# BlancerCarMotoDriver.net
KiCad netlist of a schematic drawn in Altium Designer
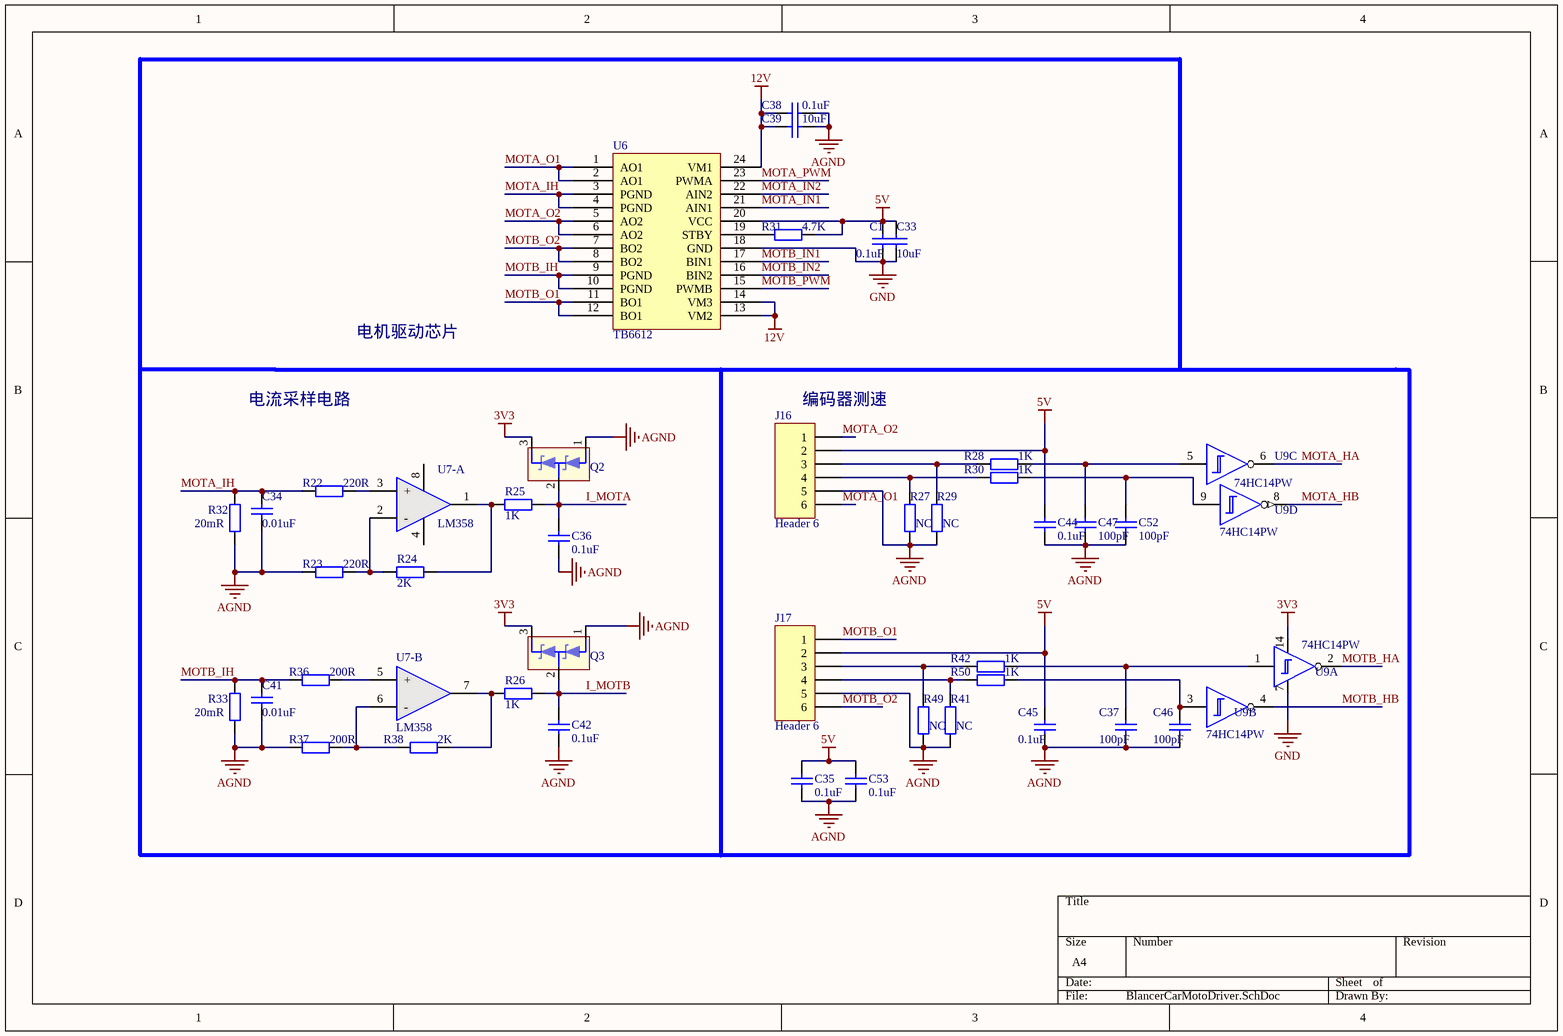
[diagram p0: BlancerCarMotoDriver.SchDoc]

(export (version "E")
  (design (tool "Eeschema 10.0.6"))
  (components
    (comp (ref "C1")
      (value "0.1uF")
      (footprint "0805-1")
      (description "Capacitor")
      (fields (field (name "Comment") "Cap") (field (name "PUBLISHER") "Altium Limited"))
      (libsource (lib "BlancerCar") (part "Cap"))
    )
    (comp (ref "C33")
      (value "10uF")
      (footprint "0805-1")
      (description "Capacitor")
      (fields (field (name "Comment") "Cap") (field (name "PUBLISHER") "Altium Limited"))
      (libsource (lib "BlancerCar") (part "Cap"))
    )
    (comp (ref "C34")
      (value "0.01uF")
      (footprint "0805-1")
      (description "Capacitor")
      (fields (field (name "Comment") "Cap") (field (name "PUBLISHER") "Altium Limited"))
      (libsource (lib "BlancerCar") (part "Cap"))
    )
    (comp (ref "C35")
      (value "0.1uF")
      (footprint "0805-1")
      (description "Capacitor")
      (fields (field (name "Comment") "Cap") (field (name "PUBLISHER") "Altium Limited"))
      (libsource (lib "BlancerCar") (part "Cap"))
    )
    (comp (ref "C36")
      (value "0.1uF")
      (footprint "0805-1")
      (description "Capacitor")
      (fields (field (name "Comment") "Cap") (field (name "PUBLISHER") "Altium Limited"))
      (libsource (lib "BlancerCar") (part "Cap"))
    )
    (comp (ref "C37")
      (value "100pF")
      (footprint "0805-1")
      (description "Capacitor")
      (fields (field (name "Comment") "Cap") (field (name "PUBLISHER") "Altium Limited"))
      (libsource (lib "BlancerCar") (part "Cap"))
    )
    (comp (ref "C38")
      (value "0.1uF")
      (footprint "0805-1")
      (description "Capacitor")
      (fields (field (name "Comment") "Cap") (field (name "PUBLISHER") "Altium Limited"))
      (libsource (lib "BlancerCar") (part "Cap"))
    )
    (comp (ref "C39")
      (value "10uF")
      (footprint "0805-1")
      (description "Capacitor")
      (fields (field (name "Comment") "Cap") (field (name "PUBLISHER") "Altium Limited"))
      (libsource (lib "BlancerCar") (part "Cap"))
    )
    (comp (ref "C41")
      (value "0.01uF")
      (footprint "0805-1")
      (description "Capacitor")
      (fields (field (name "Comment") "Cap") (field (name "PUBLISHER") "Altium Limited"))
      (libsource (lib "BlancerCar") (part "Cap"))
    )
    (comp (ref "C42")
      (value "0.1uF")
      (footprint "0805-1")
      (description "Capacitor")
      (fields (field (name "Comment") "Cap") (field (name "PUBLISHER") "Altium Limited"))
      (libsource (lib "BlancerCar") (part "Cap"))
    )
    (comp (ref "C44")
      (value "0.1uF")
      (footprint "0805-1")
      (description "Capacitor")
      (fields (field (name "Comment") "Cap") (field (name "PUBLISHER") "Altium Limited"))
      (libsource (lib "BlancerCar") (part "Cap"))
    )
    (comp (ref "C45")
      (value "0.1uF")
      (footprint "0805-1")
      (description "Capacitor")
      (fields (field (name "Comment") "Cap") (field (name "PUBLISHER") "Altium Limited"))
      (libsource (lib "BlancerCar") (part "Cap"))
    )
    (comp (ref "C46")
      (value "100pF")
      (footprint "0805-1")
      (description "Capacitor")
      (fields (field (name "Comment") "Cap") (field (name "PUBLISHER") "Altium Limited"))
      (libsource (lib "BlancerCar") (part "Cap"))
    )
    (comp (ref "C47")
      (value "100pF")
      (footprint "0805-1")
      (description "Capacitor")
      (fields (field (name "Comment") "Cap") (field (name "PUBLISHER") "Altium Limited"))
      (libsource (lib "BlancerCar") (part "Cap"))
    )
    (comp (ref "C52")
      (value "100pF")
      (footprint "0805-1")
      (description "Capacitor")
      (fields (field (name "Comment") "Cap") (field (name "PUBLISHER") "Altium Limited"))
      (libsource (lib "BlancerCar") (part "Cap"))
    )
    (comp (ref "C53")
      (value "0.1uF")
      (footprint "0805-1")
      (description "Capacitor")
      (fields (field (name "Comment") "Cap") (field (name "PUBLISHER") "Altium Limited"))
      (libsource (lib "BlancerCar") (part "Cap"))
    )
    (comp (ref "J16")
      (value "Header 6")
      (footprint "HDR1X6")
      (description "Header, 6-Pin")
      (fields (field (name "PUBLISHER") "Altium Limited"))
      (libsource (lib "Miscellaneous Connectors") (part "Header 6"))
    )
    (comp (ref "J17")
      (value "Header 6")
      (footprint "HDR1X6")
      (description "Header, 6-Pin")
      (fields (field (name "PUBLISHER") "Altium Limited"))
      (libsource (lib "Miscellaneous Connectors") (part "Header 6"))
    )
    (comp (ref "Q2")
      (value "肖基特二极管")
      (footprint "BAT54S(SOT-23-3)")
      (libsource (lib "BlancerCar") (part "BAT54S"))
    )
    (comp (ref "Q3")
      (value "肖基特二极管")
      (footprint "BAT54S(SOT-23-3)")
      (libsource (lib "BlancerCar") (part "BAT54S"))
    )
    (comp (ref "R22")
      (value "220R")
      (footprint "0805-1")
      (description "贴片电阻")
      (fields (field (name "Comment") "Res1") (field (name "PUBLISHER") "Altium Limited"))
      (libsource (lib "xdhADL") (part "Res1"))
    )
    (comp (ref "R23")
      (value "220R")
      (footprint "0805-1")
      (description "贴片电阻")
      (fields (field (name "Comment") "Res1") (field (name "PUBLISHER") "Altium Limited"))
      (libsource (lib "xdhADL") (part "Res1"))
    )
    (comp (ref "R24")
      (value "2K")
      (footprint "0805-1")
      (description "贴片电阻")
      (fields (field (name "Comment") "Res1") (field (name "PUBLISHER") "Altium Limited"))
      (libsource (lib "xdhADL") (part "Res1"))
    )
    (comp (ref "R25")
      (value "1K")
      (footprint "0805-1")
      (description "贴片电阻")
      (fields (field (name "Comment") "Res1") (field (name "PUBLISHER") "Altium Limited"))
      (libsource (lib "xdhADL") (part "Res1"))
    )
    (comp (ref "R26")
      (value "1K")
      (footprint "0805-1")
      (description "贴片电阻")
      (fields (field (name "Comment") "Res1") (field (name "PUBLISHER") "Altium Limited"))
      (libsource (lib "") (part "Res1_1"))
    )
    (comp (ref "R27")
      (value "NC")
      (footprint "0805-1")
      (description "贴片电阻")
      (fields (field (name "Comment") "Res1") (field (name "PUBLISHER") "Altium Limited"))
      (libsource (lib "") (part "Res1_2"))
    )
    (comp (ref "R28")
      (value "1K")
      (footprint "0805-1")
      (description "贴片电阻")
      (fields (field (name "Comment") "Res1") (field (name "PUBLISHER") "Altium Limited"))
      (libsource (lib "xdhADL") (part "Res1"))
    )
    (comp (ref "R29")
      (value "NC")
      (footprint "0805-1")
      (description "贴片电阻")
      (fields (field (name "Comment") "Res1") (field (name "PUBLISHER") "Altium Limited"))
      (libsource (lib "") (part "Res1_2"))
    )
    (comp (ref "R30")
      (value "1K")
      (footprint "0805-1")
      (description "贴片电阻")
      (fields (field (name "Comment") "Res1") (field (name "PUBLISHER") "Altium Limited"))
      (libsource (lib "xdhADL") (part "Res1"))
    )
    (comp (ref "R31")
      (value "4.7K")
      (footprint "0805-1")
      (description "贴片电阻")
      (fields (field (name "Comment") "Res1") (field (name "PUBLISHER") "Altium Limited"))
      (libsource (lib "xdhADL") (part "Res1"))
    )
    (comp (ref "R32")
      (value "20mR")
      (footprint "0805-1")
      (description "贴片电阻")
      (fields (field (name "Comment") "Res1") (field (name "PUBLISHER") "Altium Limited"))
      (libsource (lib "xdhADL") (part "Res1"))
    )
    (comp (ref "R33")
      (value "20mR")
      (footprint "0805-1")
      (description "贴片电阻")
      (fields (field (name "Comment") "Res1") (field (name "PUBLISHER") "Altium Limited"))
      (libsource (lib "") (part "Res1_2"))
    )
    (comp (ref "R36")
      (value "200R")
      (footprint "0805-1")
      (description "贴片电阻")
      (fields (field (name "Comment") "Res1") (field (name "PUBLISHER") "Altium Limited"))
      (libsource (lib "") (part "Res1_1"))
    )
    (comp (ref "R37")
      (value "200R")
      (footprint "0805-1")
      (description "贴片电阻")
      (fields (field (name "Comment") "Res1") (field (name "PUBLISHER") "Altium Limited"))
      (libsource (lib "") (part "Res1_1"))
    )
    (comp (ref "R38")
      (value "2K")
      (footprint "0805-1")
      (description "贴片电阻")
      (fields (field (name "Comment") "Res1") (field (name "PUBLISHER") "Altium Limited"))
      (libsource (lib "") (part "Res1_1"))
    )
    (comp (ref "R41")
      (value "NC")
      (footprint "0805-1")
      (description "贴片电阻")
      (fields (field (name "Comment") "Res1") (field (name "PUBLISHER") "Altium Limited"))
      (libsource (lib "") (part "Res1_2"))
    )
    (comp (ref "R42")
      (value "1K")
      (footprint "0805-1")
      (description "贴片电阻")
      (fields (field (name "Comment") "Res1") (field (name "PUBLISHER") "Altium Limited"))
      (libsource (lib "xdhADL") (part "Res1"))
    )
    (comp (ref "R49")
      (value "NC")
      (footprint "0805-1")
      (description "贴片电阻")
      (fields (field (name "Comment") "Res1") (field (name "PUBLISHER") "Altium Limited"))
      (libsource (lib "") (part "Res1_2"))
    )
    (comp (ref "R50")
      (value "1K")
      (footprint "0805-1")
      (description "贴片电阻")
      (fields (field (name "Comment") "Res1") (field (name "PUBLISHER") "Altium Limited"))
      (libsource (lib "xdhADL") (part "Res1"))
    )
    (comp (ref "U6") (value "TB6612") (footprint "TB6612") (libsource (lib "BlancerCar") (part "TB6612")))
    (comp (ref "U7-")
      (value "LM358")
      (footprint "NSO8_N")
      (description "双运放")
      (libsource (lib "*") (part "LM358"))
    )
    (comp (ref "U9")
      (value "74HC14PW")
      (footprint "SSOP-14")
      (description "6非门")
      (libsource (lib "xdhADL") (part "74HC14PW"))
    )
  )
  (nets
    (net (code "1") (name "/I_MOTA") (class "Default")
      (node (ref "C36") (pin "2") (pinfunction "2_2") (pintype "passive"))
      (node (ref "Q2") (pin "2") (pinfunction "2_2") (pintype "passive"))
      (node (ref "R25") (pin "2") (pinfunction "2_2") (pintype "passive"))
    )
    (net (code "2") (name "/I_MOTB") (class "Default")
      (node (ref "C42") (pin "2") (pinfunction "2_2") (pintype "passive"))
      (node (ref "Q3") (pin "2") (pinfunction "2_2") (pintype "passive"))
      (node (ref "R26") (pin "1") (pinfunction "1_1") (pintype "passive"))
    )
    (net (code "3") (name "/MOTA_HA") (class "Default")
      (node (ref "U9") (pin "6") (pinfunction "Y_6") (pintype "passive"))
    )
    (net (code "4") (name "/MOTA_HB") (class "Default")
      (node (ref "U9") (pin "8") (pinfunction "Y_8") (pintype "output"))
    )
    (net (code "5") (name "/MOTA_IH") (class "Default")
      (node (ref "C34") (pin "2") (pinfunction "2_2") (pintype "passive"))
      (node (ref "R22") (pin "1") (pinfunction "1_1") (pintype "passive"))
      (node (ref "R32") (pin "2") (pinfunction "2_2") (pintype "passive"))
      (node (ref "U6") (pin "3") (pinfunction "PGND_3") (pintype "passive"))
      (node (ref "U6") (pin "4") (pinfunction "PGND_4") (pintype "passive"))
    )
    (net (code "6") (name "/MOTA_IN1") (class "Default")
      (node (ref "U6") (pin "21") (pinfunction "AIN1_21") (pintype "passive"))
    )
    (net (code "7") (name "/MOTA_IN2") (class "Default")
      (node (ref "U6") (pin "22") (pinfunction "AIN2_22") (pintype "passive"))
    )
    (net (code "8") (name "/MOTA_O1") (class "Default")
      (node (ref "J16") (pin "6") (pinfunction "6_6") (pintype "passive"))
      (node (ref "U6") (pin "1") (pinfunction "AO1_1") (pintype "passive"))
      (node (ref "U6") (pin "2") (pinfunction "AO1_2") (pintype "passive"))
    )
    (net (code "9") (name "/MOTA_O2") (class "Default")
      (node (ref "J16") (pin "1") (pinfunction "1_1") (pintype "passive"))
      (node (ref "U6") (pin "5") (pinfunction "AO2_5") (pintype "passive"))
      (node (ref "U6") (pin "6") (pinfunction "AO2_6") (pintype "passive"))
    )
    (net (code "10") (name "/MOTA_PWM") (class "Default")
      (node (ref "U6") (pin "23") (pinfunction "PWMA_23") (pintype "passive"))
    )
    (net (code "11") (name "/MOTB_HA") (class "Default")
      (node (ref "U9") (pin "2") (pinfunction "Y_2") (pintype "passive"))
    )
    (net (code "12") (name "/MOTB_HB") (class "Default")
      (node (ref "U9") (pin "4") (pinfunction "Y_4") (pintype "passive"))
    )
    (net (code "13") (name "/MOTB_IH") (class "Default")
      (node (ref "C41") (pin "2") (pinfunction "2_2") (pintype "passive"))
      (node (ref "R33") (pin "2") (pinfunction "2_2") (pintype "passive"))
      (node (ref "R36") (pin "2") (pinfunction "2_2") (pintype "passive"))
      (node (ref "U6") (pin "10") (pinfunction "PGND_10") (pintype "passive"))
      (node (ref "U6") (pin "9") (pinfunction "PGND_9") (pintype "passive"))
    )
    (net (code "14") (name "/MOTB_IN1") (class "Default")
      (node (ref "U6") (pin "17") (pinfunction "BIN1_17") (pintype "passive"))
    )
    (net (code "15") (name "/MOTB_IN2") (class "Default")
      (node (ref "U6") (pin "16") (pinfunction "BIN2_16") (pintype "passive"))
    )
    (net (code "16") (name "/MOTB_O1") (class "Default")
      (node (ref "J17") (pin "1") (pinfunction "1_1") (pintype "passive"))
      (node (ref "U6") (pin "11") (pinfunction "BO1_11") (pintype "passive"))
      (node (ref "U6") (pin "12") (pinfunction "BO1_12") (pintype "passive"))
    )
    (net (code "17") (name "/MOTB_O2") (class "Default")
      (node (ref "J17") (pin "6") (pinfunction "6_6") (pintype "passive"))
      (node (ref "U6") (pin "7") (pinfunction "BO2_7") (pintype "passive"))
      (node (ref "U6") (pin "8") (pinfunction "BO2_8") (pintype "passive"))
    )
    (net (code "18") (name "/MOTB_PWM") (class "Default")
      (node (ref "U6") (pin "15") (pinfunction "PWMB_15") (pintype "passive"))
    )
    (net (code "19") (name "3V3") (class "Default")
      (node (ref "Q2") (pin "3") (pinfunction "3_3") (pintype "passive"))
      (node (ref "Q3") (pin "3") (pinfunction "3_3") (pintype "passive"))
      (node (ref "U9") (pin "14") (pinfunction "VCC_14") (pintype "power_in"))
    )
    (net (code "20") (name "5V") (class "Default")
      (node (ref "C1") (pin "2") (pinfunction "2_2") (pintype "passive"))
      (node (ref "C33") (pin "2") (pinfunction "2_2") (pintype "passive"))
      (node (ref "C35") (pin "2") (pinfunction "2_2") (pintype "passive"))
      (node (ref "C44") (pin "2") (pinfunction "2_2") (pintype "passive"))
      (node (ref "C45") (pin "2") (pinfunction "2_2") (pintype "passive"))
      (node (ref "C53") (pin "2") (pinfunction "2_2") (pintype "passive"))
      (node (ref "J16") (pin "2") (pinfunction "2_2") (pintype "passive"))
      (node (ref "J17") (pin "2") (pinfunction "2_2") (pintype "passive"))
      (node (ref "R31") (pin "2") (pinfunction "2_2") (pintype "passive"))
      (node (ref "U6") (pin "20") (pinfunction "VCC_20") (pintype "passive"))
    )
    (net (code "21") (name "12V") (class "Default")
      (node (ref "C38") (pin "1") (pinfunction "1_1") (pintype "passive"))
      (node (ref "C39") (pin "1") (pinfunction "1_1") (pintype "passive"))
      (node (ref "U6") (pin "13") (pinfunction "VM2_13") (pintype "passive"))
      (node (ref "U6") (pin "14") (pinfunction "VM3_14") (pintype "passive"))
      (node (ref "U6") (pin "24") (pinfunction "VM1_24") (pintype "passive"))
    )
    (net (code "22") (name "AGND") (class "Default")
      (node (ref "C34") (pin "1") (pinfunction "1_1") (pintype "passive"))
      (node (ref "C35") (pin "1") (pinfunction "1_1") (pintype "passive"))
      (node (ref "C36") (pin "1") (pinfunction "1_1") (pintype "passive"))
      (node (ref "C37") (pin "1") (pinfunction "1_1") (pintype "passive"))
      (node (ref "C38") (pin "2") (pinfunction "2_2") (pintype "passive"))
      (node (ref "C39") (pin "2") (pinfunction "2_2") (pintype "passive"))
      (node (ref "C41") (pin "1") (pinfunction "1_1") (pintype "passive"))
      (node (ref "C42") (pin "1") (pinfunction "1_1") (pintype "passive"))
      (node (ref "C44") (pin "1") (pinfunction "1_1") (pintype "passive"))
      (node (ref "C45") (pin "1") (pinfunction "1_1") (pintype "passive"))
      (node (ref "C46") (pin "1") (pinfunction "1_1") (pintype "passive"))
      (node (ref "C47") (pin "1") (pinfunction "1_1") (pintype "passive"))
      (node (ref "C52") (pin "1") (pinfunction "1_1") (pintype "passive"))
      (node (ref "C53") (pin "1") (pinfunction "1_1") (pintype "passive"))
      (node (ref "J16") (pin "5") (pinfunction "5_5") (pintype "passive"))
      (node (ref "J17") (pin "5") (pinfunction "5_5") (pintype "passive"))
      (node (ref "Q2") (pin "1") (pinfunction "1_1") (pintype "passive"))
      (node (ref "Q3") (pin "1") (pinfunction "1_1") (pintype "passive"))
      (node (ref "R23") (pin "1") (pinfunction "1_1") (pintype "passive"))
      (node (ref "R27") (pin "1") (pinfunction "1_1") (pintype "passive"))
      (node (ref "R29") (pin "1") (pinfunction "1_1") (pintype "passive"))
      (node (ref "R32") (pin "1") (pinfunction "1_1") (pintype "passive"))
      (node (ref "R33") (pin "1") (pinfunction "1_1") (pintype "passive"))
      (node (ref "R37") (pin "2") (pinfunction "2_2") (pintype "passive"))
      (node (ref "R41") (pin "1") (pinfunction "1_1") (pintype "passive"))
      (node (ref "R49") (pin "1") (pinfunction "1_1") (pintype "passive"))
    )
    (net (code "23") (name "GND") (class "Default")
      (node (ref "C1") (pin "1") (pinfunction "1_1") (pintype "passive"))
      (node (ref "C33") (pin "1") (pinfunction "1_1") (pintype "passive"))
      (node (ref "U6") (pin "18") (pinfunction "GND_18") (pintype "passive"))
      (node (ref "U9") (pin "7") (pinfunction "15_7") (pintype "power_in"))
    )
    (net (code "24") (name "Net-(J16-Pad3)") (class "Default")
      (node (ref "J16") (pin "3") (pinfunction "3_3") (pintype "passive"))
      (node (ref "R28") (pin "1") (pinfunction "1_1") (pintype "passive"))
      (node (ref "R29") (pin "2") (pinfunction "2_2") (pintype "passive"))
    )
    (net (code "25") (name "Net-(J16-Pad4)") (class "Default")
      (node (ref "J16") (pin "4") (pinfunction "4_4") (pintype "passive"))
      (node (ref "R27") (pin "2") (pinfunction "2_2") (pintype "passive"))
      (node (ref "R30") (pin "1") (pinfunction "1_1") (pintype "passive"))
    )
    (net (code "26") (name "Net-(J17-Pad3)") (class "Default")
      (node (ref "J17") (pin "3") (pinfunction "3_3") (pintype "passive"))
      (node (ref "R42") (pin "1") (pinfunction "1_1") (pintype "passive"))
      (node (ref "R49") (pin "2") (pinfunction "2_2") (pintype "passive"))
    )
    (net (code "27") (name "Net-(J17-Pad4)") (class "Default")
      (node (ref "J17") (pin "4") (pinfunction "4_4") (pintype "passive"))
      (node (ref "R41") (pin "2") (pinfunction "2_2") (pintype "passive"))
      (node (ref "R50") (pin "1") (pinfunction "1_1") (pintype "passive"))
    )
    (net (code "28") (name "Net-(U6-STBY)") (class "Default")
      (node (ref "R31") (pin "1") (pinfunction "1_1") (pintype "passive"))
      (node (ref "U6") (pin "19") (pinfunction "STBY_19") (pintype "passive"))
    )
    (net (code "29") (name "Net-(U7-A-+)") (class "Default")
      (node (ref "R22") (pin "2") (pinfunction "2_2") (pintype "passive"))
      (node (ref "U7-") (pin "3") (pinfunction "+_3") (pintype "passive"))
    )
    (net (code "30") (name "Net-(U7-A--)") (class "Default")
      (node (ref "R23") (pin "2") (pinfunction "2_2") (pintype "passive"))
      (node (ref "R24") (pin "1") (pinfunction "1_1") (pintype "passive"))
      (node (ref "U7-") (pin "2") (pinfunction "-_2") (pintype "passive"))
    )
    (net (code "31") (name "Net-(U7-A-OUT1)") (class "Default")
      (node (ref "R24") (pin "2") (pinfunction "2_2") (pintype "passive"))
      (node (ref "R25") (pin "1") (pinfunction "1_1") (pintype "passive"))
      (node (ref "U7-") (pin "1") (pinfunction "OUT1_1") (pintype "passive"))
    )
    (net (code "32") (name "Net-(U7-B-+)") (class "Default")
      (node (ref "R36") (pin "1") (pinfunction "1_1") (pintype "passive"))
      (node (ref "U7-") (pin "5") (pinfunction "+_5") (pintype "passive"))
    )
    (net (code "33") (name "Net-(U7-B--)") (class "Default")
      (node (ref "R37") (pin "1") (pinfunction "1_1") (pintype "passive"))
      (node (ref "R38") (pin "2") (pinfunction "2_2") (pintype "passive"))
      (node (ref "U7-") (pin "6") (pinfunction "-_6") (pintype "passive"))
    )
    (net (code "34") (name "Net-(U7-B-OUT2)") (class "Default")
      (node (ref "R26") (pin "2") (pinfunction "2_2") (pintype "passive"))
      (node (ref "R38") (pin "1") (pinfunction "1_1") (pintype "passive"))
      (node (ref "U7-") (pin "7") (pinfunction "OUT2_7") (pintype "passive"))
    )
    (net (code "35") (name "Net-(U9A-A)") (class "Default")
      (node (ref "C37") (pin "2") (pinfunction "2_2") (pintype "passive"))
      (node (ref "R42") (pin "2") (pinfunction "2_2") (pintype "passive"))
      (node (ref "U9") (pin "1") (pinfunction "A_1") (pintype "passive"))
    )
    (net (code "36") (name "Net-(U9B-A)") (class "Default")
      (node (ref "C46") (pin "2") (pinfunction "2_2") (pintype "passive"))
      (node (ref "R50") (pin "2") (pinfunction "2_2") (pintype "passive"))
      (node (ref "U9") (pin "3") (pinfunction "A_3") (pintype "passive"))
    )
    (net (code "37") (name "Net-(U9C-A)") (class "Default")
      (node (ref "C47") (pin "2") (pinfunction "2_2") (pintype "passive"))
      (node (ref "R28") (pin "2") (pinfunction "2_2") (pintype "passive"))
      (node (ref "U9") (pin "5") (pinfunction "A_5") (pintype "passive"))
    )
    (net (code "38") (name "Net-(U9D-A)") (class "Default")
      (node (ref "C52") (pin "2") (pinfunction "2_2") (pintype "passive"))
      (node (ref "R30") (pin "2") (pinfunction "2_2") (pintype "passive"))
      (node (ref "U9") (pin "9") (pinfunction "A_9") (pintype "passive"))
    )
    (net (code "39") (name "unconnected-(U7-A-V+-Pad8)") (class "Default")
      (node (ref "U7-") (pin "8") (pinfunction "V+_8") (pintype "power_in"))
    )
    (net (code "40") (name "unconnected-(U7-A-V--Pad4)") (class "Default")
      (node (ref "U7-") (pin "4") (pinfunction "V-_4") (pintype "power_in"))
    )
  )
)
